# MIRA016-CSP-Sheet1.net
KiCad netlist of a schematic drawn in Altium Designer
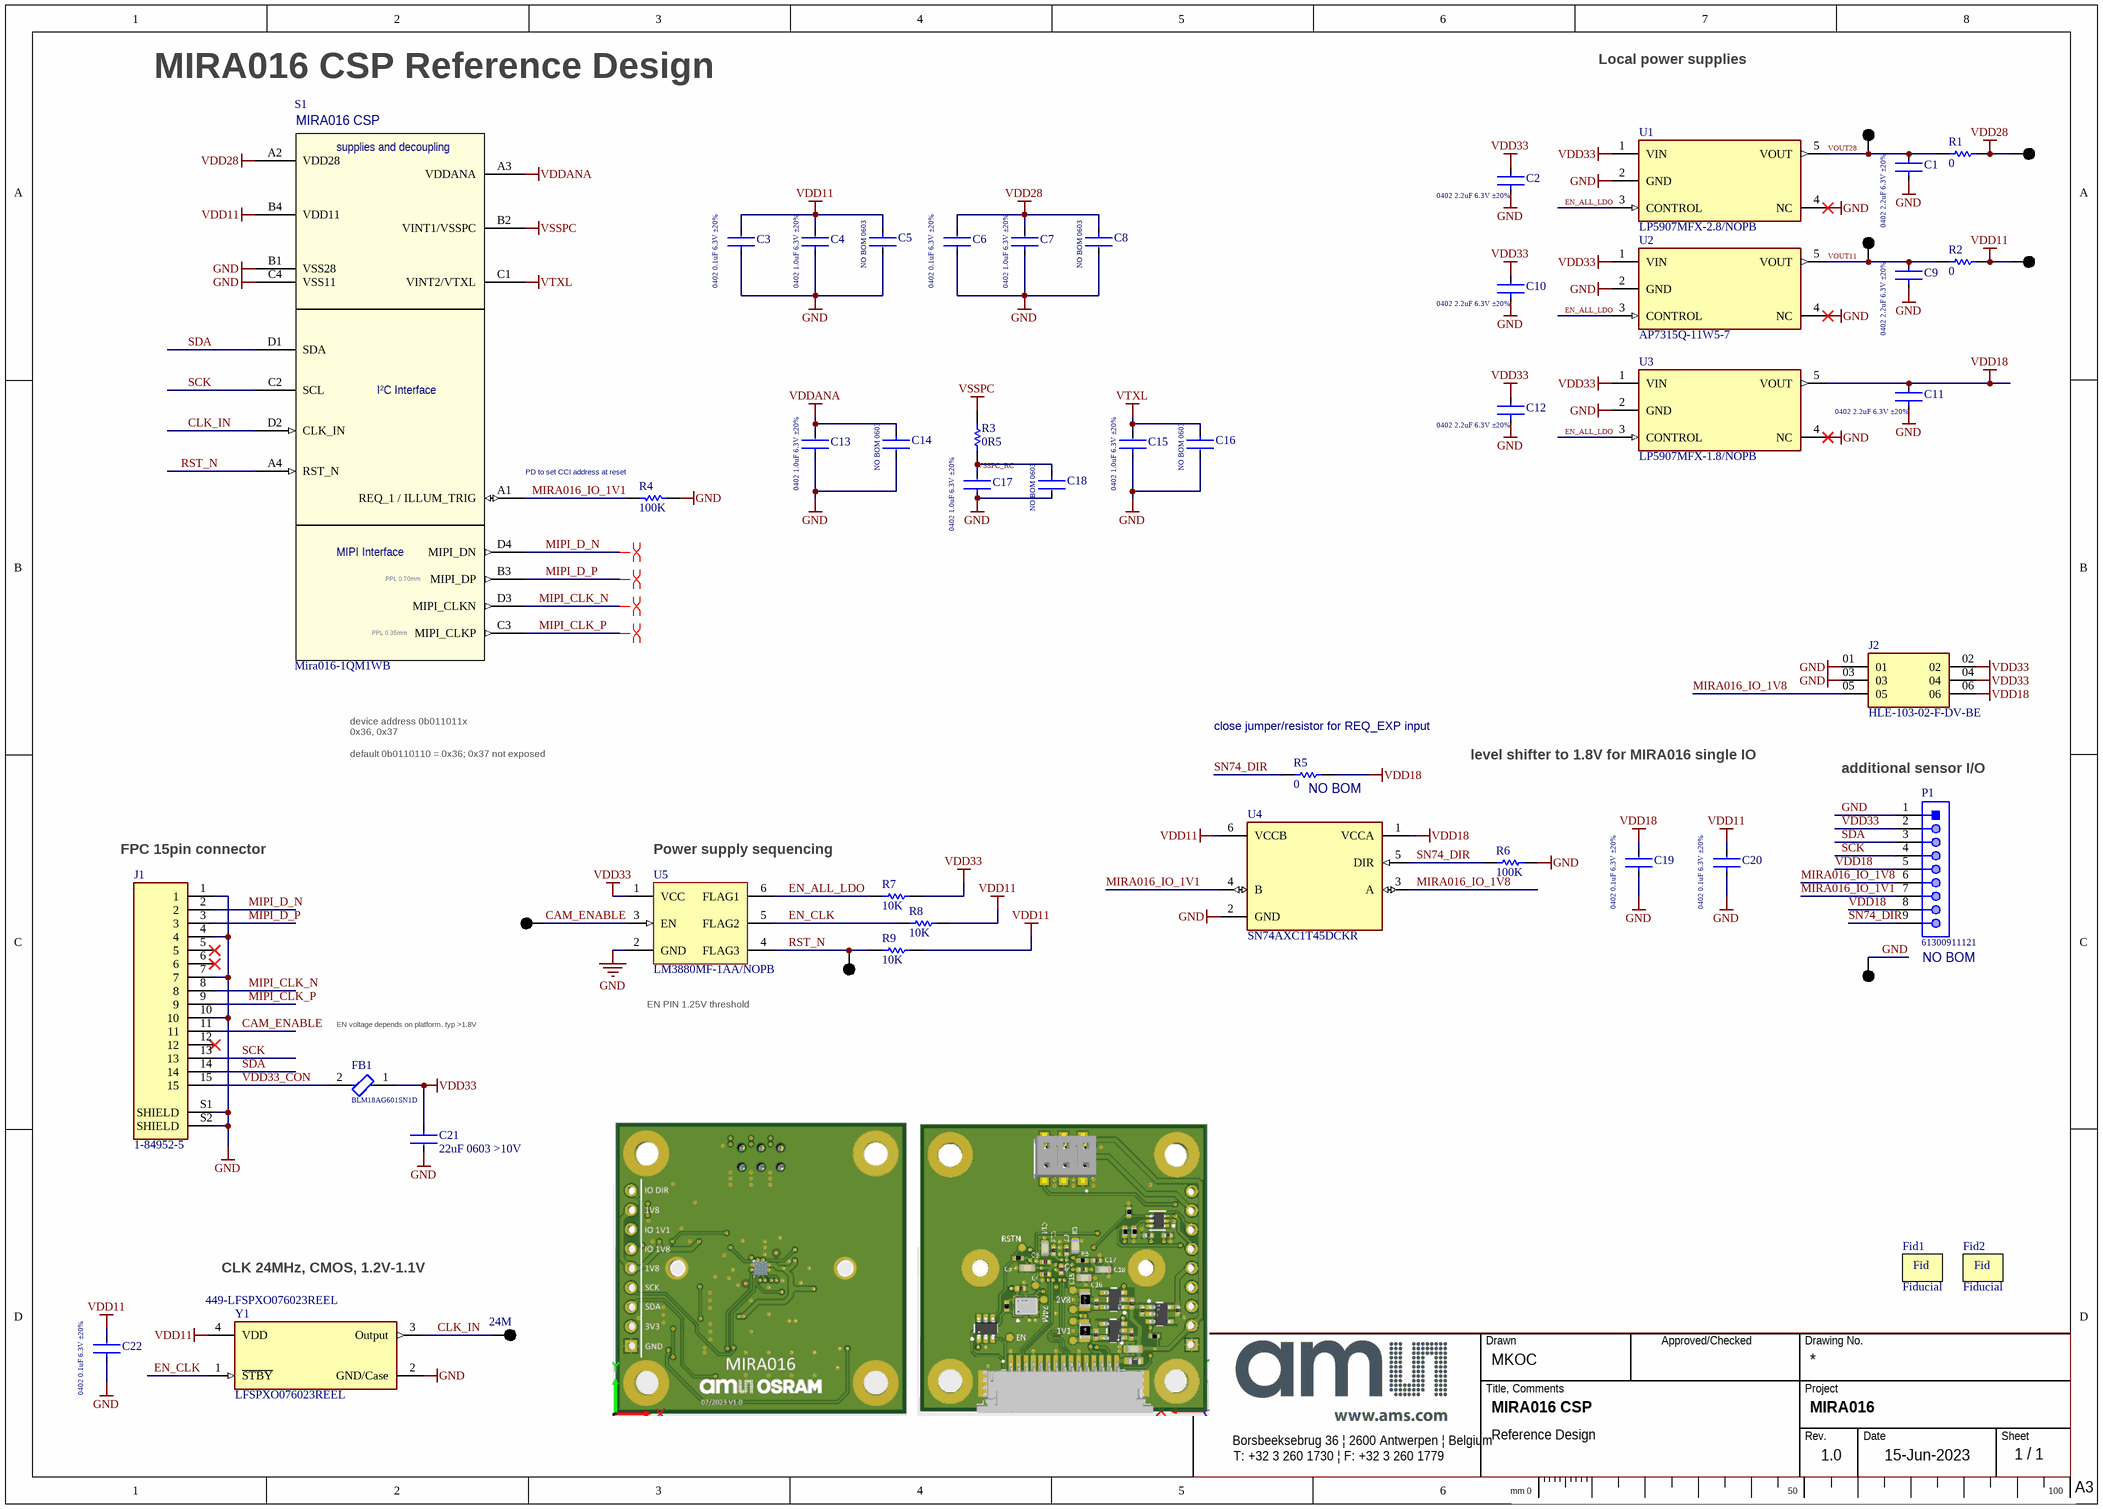
[diagram p0: MIRA016-CSP-Sheet1.SchDoc]

(export (version "E")
  (design (tool "Eeschema 10.0.6"))
  (components
    (comp (ref "C1")
      (value "0402 2.2uF 6.3V ±20%")
      (footprint "CAPC0402_N")
      (description "0402 2.20uF 6.3V ±20%")
      (libsource (lib "MIRA016-COB") (part "CAP0201"))
    )
    (comp (ref "C2")
      (value "0402 2.2uF 6.3V ±20%")
      (footprint "CAPC0402_N")
      (description "0402 2.20uF 6.3V ±20%")
      (libsource (lib "MIRA016-COB") (part "CAP0201"))
    )
    (comp (ref "C3")
      (value "0402 0.1uF 6.3V ±20%")
      (footprint "CAPC0402_N")
      (libsource (lib "MIRA016-COB") (part "CAP0201"))
    )
    (comp (ref "C4")
      (value "0402 1.0uF 6.3V ±20%")
      (footprint "CAPC0402_N")
      (libsource (lib "MIRA016-COB") (part "CAP0201"))
    )
    (comp (ref "C5")
      (value "NO BOM 0603")
      (footprint "CAPC0603_L")
      (description "spare cap 0603")
      (libsource (lib "MIRA016-CSP") (part "CAP0201"))
    )
    (comp (ref "C6")
      (value "0402 0.1uF 6.3V ±20%")
      (footprint "CAPC0402_N")
      (libsource (lib "MIRA016-COB") (part "CAP0201"))
    )
    (comp (ref "C7")
      (value "0402 1.0uF 6.3V ±20%")
      (footprint "CAPC0402_N")
      (libsource (lib "MIRA016-COB") (part "CAP0201"))
    )
    (comp (ref "C8")
      (value "NO BOM 0603")
      (footprint "CAPC0603_L")
      (description "spare cap 0603")
      (libsource (lib "MIRA016-CSP") (part "CAP0201"))
    )
    (comp (ref "C9")
      (value "0402 2.2uF 6.3V ±20%")
      (footprint "CAPC0402_N")
      (description "0402 2.20uF 6.3V ±20%")
      (libsource (lib "MIRA016-COB") (part "CAP0201"))
    )
    (comp (ref "C10")
      (value "0402 2.2uF 6.3V ±20%")
      (footprint "CAPC0402_N")
      (description "0402 2.20uF 6.3V ±20%")
      (libsource (lib "MIRA016-COB") (part "CAP0201"))
    )
    (comp (ref "C11")
      (value "0402 2.2uF 6.3V ±20%")
      (footprint "CAPC0402_N")
      (description "0402 2.20uF 6.3V ±20%")
      (libsource (lib "MIRA016-COB") (part "CAP0201"))
    )
    (comp (ref "C12")
      (value "0402 2.2uF 6.3V ±20%")
      (footprint "CAPC0402_N")
      (description "0402 2.20uF 6.3V ±20%")
      (libsource (lib "MIRA016-COB") (part "CAP0201"))
    )
    (comp (ref "C13")
      (value "0402 1.0uF 6.3V ±20%")
      (footprint "CAPC0402_N")
      (libsource (lib "MIRA016-COB") (part "CAP0201"))
    )
    (comp (ref "C14")
      (value "NO BOM 0603")
      (footprint "CAPC0603_L")
      (description "spare cap 0603")
      (libsource (lib "MIRA016-CSP") (part "CAP0201"))
    )
    (comp (ref "C15")
      (value "0402 1.0uF 6.3V ±20%")
      (footprint "CAPC0402_N")
      (libsource (lib "MIRA016-COB") (part "CAP0201"))
    )
    (comp (ref "C16")
      (value "NO BOM 0603")
      (footprint "CAPC0603_L")
      (description "spare cap 0603")
      (libsource (lib "MIRA016-CSP") (part "CAP0201"))
    )
    (comp (ref "C17")
      (value "0402 1.0uF 6.3V ±20%")
      (footprint "CAPC0402_N")
      (libsource (lib "MIRA016-COB") (part "CAP0201"))
    )
    (comp (ref "C18")
      (value "NO BOM 0603")
      (footprint "CAPC0603_L")
      (description "spare cap 0603")
      (libsource (lib "MIRA016-CSP") (part "CAP0201"))
    )
    (comp (ref "C19")
      (value "0402 0.1uF 6.3V ±20%")
      (footprint "CAPC0402_N")
      (libsource (lib "MIRA016-COB") (part "CAP0201"))
    )
    (comp (ref "C20")
      (value "0402 0.1uF 6.3V ±20%")
      (footprint "CAPC0402_N")
      (libsource (lib "MIRA016-COB") (part "CAP0201"))
    )
    (comp (ref "C21")
      (value "22uF 0603 >10V")
      (footprint "CAPC0603")
      (description "Chip Multilayer Ceramic Capacitors for General Purpose, 0603, 22uF, X5R, 15%, 10%, 25V")
      (libsource (lib "MIRA016-CSP") (part "CAP0201"))
    )
    (comp (ref "C22")
      (value "0402 0.1uF 6.3V ±20%")
      (footprint "CAPC0402_N")
      (libsource (lib "MIRA016-COB") (part "CAP0201"))
    )
    (comp (ref "FB1")
      (value "BLM18AG601SN1D")
      (footprint "FP-BLM18-0_15-t0_8-IPC_B")
      (description "Chip Ferrite Bead, 0603, 600Ω @ 100MHz, 0.38Ω, 25%, 500mA")
      (fields (field (name "TOLERANCE") "25%"))
      (libsource (lib "MIRA050CSP") (part "CMP-0686-00436-3"))
    )
    (comp (ref "Fid1")
      (value "Fiducial")
      (footprint "Fiducial")
      (description "Alignment feature for PCB Assembly")
      (fields (field (name "PART NUMBER") "NA"))
      (libsource (lib "altiumlib") (part "Fiducial"))
    )
    (comp (ref "Fid2")
      (value "Fiducial")
      (footprint "Fiducial")
      (description "Alignment feature for PCB Assembly")
      (fields (field (name "PART NUMBER") "NA"))
      (libsource (lib "altiumlib") (part "Fiducial"))
    )
    (comp (ref "J1")
      (value "1-84952-5")
      (footprint "TE_1-84952-5")
      (description "Conn FPC Connector SKT 15 POS 1mm Solder RA SMD T/R")
      (libsource (lib "MIRA220CSP") (part "1-84952-5"))
    )
    (comp (ref "J2")
      (value "HLE-103-02-F-DV-BE")
      (footprint "SAMTEC_HLE-103-02-F-DV-BE")
      (fields (field (name "MF") "Samtec"))
      (libsource (lib "MIRA016-CSP") (part "HLE-103-02-F-DV-BE"))
    )
    (comp (ref "P1")
      (value "61300911121")
      (footprint "61300911121")
      (description "THT Vertical Pin Header WR-PHD, Pitch 2.54 mm, Single Row, 9 pins")
      (fields (field (name "MANUFACTURER") "Wurth Elektronik") (field (name "PUBLISHER") "WurthElektronik"))
      (libsource (lib "MIRA050CSP") (part "CMP-1502-01080-1"))
    )
    (comp (ref "R1")
      (value "0")
      (footprint "RESC0805_N")
      (description "Resistor 0R 0805")
      (libsource (lib "altiumlib") (part "Res"))
    )
    (comp (ref "R2")
      (value "0")
      (footprint "RESC0805_N")
      (description "Resistor 0R 0805")
      (libsource (lib "altiumlib") (part "Res"))
    )
    (comp (ref "R3")
      (value "0R5")
      (footprint "RESC0402_N")
      (description "Resistor 0R5  0402")
      (libsource (lib "altiumlib") (part "Res"))
    )
    (comp (ref "R4")
      (value "100K")
      (footprint "RESC0402_N")
      (description "Resistor 100K 0402")
      (fields (field (name "PART NUMBER") "ERJ2RKF1502X") (field (name "TOLERANCE") "±1%"))
      (libsource (lib "altiumlib") (part "Res"))
    )
    (comp (ref "R5")
      (value "0")
      (footprint "RESC0402_N")
      (description "Resistor 0 0402")
      (fields (field (name "PART NUMBER") "ERJ2RKF1502X") (field (name "TOLERANCE") "±1%"))
      (libsource (lib "altiumlib") (part "Res"))
    )
    (comp (ref "R6")
      (value "100K")
      (footprint "RESC0402_N")
      (description "Resistor 100K 0402")
      (fields (field (name "PART NUMBER") "ERJ2RKF1502X") (field (name "TOLERANCE") "±1%"))
      (libsource (lib "altiumlib") (part "Res"))
    )
    (comp (ref "R7")
      (value "10K")
      (footprint "RESC0402_N")
      (description "Resistor 10K 0402")
      (fields (field (name "PART NUMBER") "ERJ2RKF1502X") (field (name "TOLERANCE") "±1%"))
      (libsource (lib "altiumlib") (part "Res"))
    )
    (comp (ref "R8")
      (value "10K")
      (footprint "RESC0402_N")
      (description "Resistor 10K 0402")
      (fields (field (name "PART NUMBER") "ERJ2RKF1502X") (field (name "TOLERANCE") "±1%"))
      (libsource (lib "altiumlib") (part "Res"))
    )
    (comp (ref "R9")
      (value "10K")
      (footprint "RESC0402_N")
      (description "Resistor 10K 0402")
      (fields (field (name "PART NUMBER") "ERJ2RKF1502X") (field (name "TOLERANCE") "±1%"))
      (libsource (lib "altiumlib") (part "Res"))
    )
    (comp (ref "S1")
      (value "Mira016-1QM1WB")
      (footprint "MIRA016CSP")
      (description "MIRA016 CSP")
      (libsource (lib "MIRA016-CSP") (part "MIRA016CSP"))
    )
    (comp (ref "TP1")
      (value "2V8")
      (footprint "TP_1mm")
      (description "Test Point, various footprints")
      (libsource (lib "MIRA050CSP") (part "5001"))
    )
    (comp (ref "TP2")
      (value "2V8")
      (footprint "TP_1mm")
      (description "Test Point, various footprints")
      (libsource (lib "MIRA050CSP") (part "5001"))
    )
    (comp (ref "TP3")
      (value "1V1")
      (footprint "TP_1mm")
      (description "Test Point, various footprints")
      (libsource (lib "MIRA050CSP") (part "5001"))
    )
    (comp (ref "TP4")
      (value "1V1")
      (footprint "TP_1mm")
      (description "Test Point, various footprints")
      (libsource (lib "MIRA050CSP") (part "5001"))
    )
    (comp (ref "TP6")
      (value "EN")
      (footprint "TP_1mm")
      (description "Test Point, various footprints")
      (libsource (lib "MIRA050CSP") (part "5001"))
    )
    (comp (ref "TP7")
      (value "RSTN")
      (footprint "TP_1mm")
      (description "Test Point, various footprints")
      (libsource (lib "MIRA050CSP") (part "5001"))
    )
    (comp (ref "TP8")
      (value "GND")
      (footprint "TP_1mm")
      (description "Test Point, various footprints")
      (libsource (lib "MIRA050CSP") (part "5001"))
    )
    (comp (ref "TP9")
      (value "24M")
      (footprint "TP_1mm")
      (description "Test Point, various footprints")
      (libsource (lib "MIRA050CSP") (part "5001"))
    )
    (comp (ref "U1")
      (value "LP5907MFX-2.8/NOPB")
      (footprint "FP-DBV0005A-MFG")
      (description "IC REG LINEAR fixed Voltage, SOT23-5 / SOT-25 / SC74A package")
      (libsource (lib "MIRA016-CSP") (part "LDO-STO23-5"))
    )
    (comp (ref "U2")
      (value "AP7315Q-11W5-7")
      (footprint "FP-DBV0005A-MFG")
      (description "IC REG LINEAR fixed Voltage, SOT23-5 / SOT-25 / SC74A package")
      (libsource (lib "MIRA016-CSP") (part "LDO-STO23-5"))
    )
    (comp (ref "U3")
      (value "LP5907MFX-1.8/NOPB")
      (footprint "FP-DBV0005A-MFG")
      (description "IC REG LINEAR fixed Voltage, SOT23-5 / SOT-25 / SC74A package")
      (libsource (lib "MIRA016-CSP") (part "LDO-STO23-5"))
    )
    (comp (ref "U4")
      (value "SN74AXC1T45DCKR")
      (footprint "FP-DCK0006A-IPC_B")
      (description "IC TRNSLTR BIDIRECTIONAL SC70-6")
      (libsource (lib "Altium Content Vault") (part "d0dbdffe323aa12037fe7fb072119e8"))
    )
    (comp (ref "U5")
      (value "LM3880MF-1AA/NOPB")
      (footprint "DBV0006A_N")
      (description "Power Sequencer, 6-pin SOT-23, Pb-Free, 1000 Reel")
      (libsource (lib "MIRA016-COB") (part "CMP-0063-01015-4"))
    )
    (comp (ref "Y1")
      (value "LFSPXO076023REEL")
      (footprint "FP-ASE-MFG")
      (fields
        (field (name "SUPPLIER PART NUMBER 1") "449-LFSPXO076023REEL")
        (field (name "MANUFACTURER") "IQD")
      )
      (libsource (lib "Altium Content Vault") (part "61a724e6190563596ac712fef61ad37"))
    )
  )
  (nets
    (net (code "1") (name "/CAM_ENABLE") (class "Default")
      (node (ref "J1") (pin "11") (pinfunction "11_11") (pintype "passive"))
      (node (ref "TP6") (pin "1") (pintype "passive"))
      (node (ref "U5") (pin "3") (pinfunction "EN_3") (pintype "input"))
    )
    (net (code "2") (name "/CLK_IN") (class "Default")
      (node (ref "S1") (pin "D2") (pinfunction "CLK_IN_D2") (pintype "input"))
      (node (ref "TP9") (pin "1") (pintype "passive"))
      (node (ref "Y1") (pin "3") (pinfunction "Output_3") (pintype "output"))
    )
    (net (code "3") (name "/EN_ALL_LDO") (class "Default")
      (node (ref "R7") (pin "1") (pinfunction "1_1") (pintype "passive"))
      (node (ref "U1") (pin "3") (pinfunction "CONTROL_3") (pintype "input"))
      (node (ref "U2") (pin "3") (pinfunction "CONTROL_3") (pintype "input"))
      (node (ref "U3") (pin "3") (pinfunction "CONTROL_3") (pintype "input"))
      (node (ref "U5") (pin "6") (pinfunction "FLAG1_6") (pintype "open_collector"))
    )
    (net (code "4") (name "/EN_CLK") (class "Default")
      (node (ref "R8") (pin "1") (pinfunction "1_1") (pintype "passive"))
      (node (ref "U5") (pin "5") (pinfunction "FLAG2_5") (pintype "open_collector"))
      (node (ref "Y1") (pin "1") (pinfunction "~{STBY}_1") (pintype "input"))
    )
    (net (code "5") (name "/MIPI_CLK_N") (class "Default")
      (node (ref "J1") (pin "8") (pinfunction "8_8") (pintype "passive"))
      (node (ref "S1") (pin "D3") (pinfunction "MIPI_CLKN_D3") (pintype "output"))
    )
    (net (code "6") (name "/MIPI_CLK_P") (class "Default")
      (node (ref "J1") (pin "9") (pinfunction "9_9") (pintype "passive"))
      (node (ref "S1") (pin "C3") (pinfunction "MIPI_CLKP_C3") (pintype "output"))
    )
    (net (code "7") (name "/MIPI_D_N") (class "Default")
      (node (ref "J1") (pin "2") (pinfunction "2_2") (pintype "passive"))
      (node (ref "S1") (pin "D4") (pinfunction "MIPI_DN_D4") (pintype "output"))
    )
    (net (code "8") (name "/MIPI_D_P") (class "Default")
      (node (ref "J1") (pin "3") (pinfunction "3_3") (pintype "passive"))
      (node (ref "S1") (pin "B3") (pinfunction "MIPI_DP_B3") (pintype "output"))
    )
    (net (code "9") (name "/MIRA016_IO_1V1") (class "Default")
      (node (ref "P1") (pin "7") (pinfunction "7_7") (pintype "passive"))
      (node (ref "R4") (pin "2") (pinfunction "2_2") (pintype "passive"))
      (node (ref "S1") (pin "A1") (pinfunction "REQ_1_/_ILLUM_TRIG_A1") (pintype "bidirectional"))
      (node (ref "U4") (pin "4") (pinfunction "B_4") (pintype "bidirectional"))
    )
    (net (code "10") (name "/MIRA016_IO_1V8") (class "Default")
      (node (ref "J2") (pin "05") (pinfunction "05_05") (pintype "passive"))
      (node (ref "P1") (pin "6") (pinfunction "6_6") (pintype "passive"))
      (node (ref "U4") (pin "3") (pinfunction "A_3") (pintype "bidirectional"))
    )
    (net (code "11") (name "/RST_N") (class "Default")
      (node (ref "R9") (pin "1") (pinfunction "1_1") (pintype "passive"))
      (node (ref "S1") (pin "A4") (pinfunction "RST_N_A4") (pintype "input"))
      (node (ref "TP7") (pin "1") (pintype "passive"))
      (node (ref "U5") (pin "4") (pinfunction "FLAG3_4") (pintype "open_collector"))
    )
    (net (code "12") (name "/SCK") (class "Default")
      (node (ref "J1") (pin "13") (pinfunction "13_13") (pintype "passive"))
      (node (ref "P1") (pin "4") (pinfunction "4_4") (pintype "passive"))
      (node (ref "S1") (pin "C2") (pinfunction "SCL_C2") (pintype "open_collector"))
    )
    (net (code "13") (name "/SDA") (class "Default")
      (node (ref "J1") (pin "14") (pinfunction "14_14") (pintype "passive"))
      (node (ref "P1") (pin "3") (pinfunction "3_3") (pintype "passive"))
      (node (ref "S1") (pin "D1") (pinfunction "SDA_D1") (pintype "open_collector"))
    )
    (net (code "14") (name "/SN74_DIR") (class "Default")
      (node (ref "P1") (pin "9") (pinfunction "9_9") (pintype "passive"))
      (node (ref "R5") (pin "1") (pinfunction "1_1") (pintype "passive"))
      (node (ref "R6") (pin "2") (pinfunction "2_2") (pintype "passive"))
      (node (ref "U4") (pin "5") (pinfunction "DIR_5") (pintype "input"))
    )
    (net (code "15") (name "/VDD33_CON") (class "Default")
      (node (ref "FB1") (pin "2") (pinfunction "2_2") (pintype "passive"))
      (node (ref "J1") (pin "15") (pinfunction "15_15") (pintype "passive"))
    )
    (net (code "16") (name "/VOUT11") (class "Default")
      (node (ref "C9") (pin "2") (pinfunction "2_2") (pintype "passive"))
      (node (ref "R2") (pin "2") (pinfunction "2_2") (pintype "passive"))
      (node (ref "TP3") (pin "1") (pintype "passive"))
      (node (ref "U2") (pin "5") (pinfunction "VOUT_5") (pintype "output"))
    )
    (net (code "17") (name "/VOUT28") (class "Default")
      (node (ref "C1") (pin "2") (pinfunction "2_2") (pintype "passive"))
      (node (ref "R1") (pin "2") (pinfunction "2_2") (pintype "passive"))
      (node (ref "TP1") (pin "1") (pintype "passive"))
      (node (ref "U1") (pin "5") (pinfunction "VOUT_5") (pintype "output"))
    )
    (net (code "18") (name "/VSSPC_RC") (class "Default")
      (node (ref "C17") (pin "2") (pinfunction "2_2") (pintype "passive"))
      (node (ref "C18") (pin "1") (pinfunction "1_1") (pintype "passive"))
      (node (ref "R3") (pin "1") (pinfunction "1_1") (pintype "passive"))
    )
    (net (code "19") (name "GND") (class "Default")
      (node (ref "C1") (pin "1") (pinfunction "1_1") (pintype "passive"))
      (node (ref "C10") (pin "1") (pinfunction "1_1") (pintype "passive"))
      (node (ref "C11") (pin "1") (pinfunction "1_1") (pintype "passive"))
      (node (ref "C12") (pin "1") (pinfunction "1_1") (pintype "passive"))
      (node (ref "C13") (pin "1") (pinfunction "1_1") (pintype "passive"))
      (node (ref "C14") (pin "2") (pinfunction "2_2") (pintype "passive"))
      (node (ref "C15") (pin "1") (pinfunction "1_1") (pintype "passive"))
      (node (ref "C16") (pin "2") (pinfunction "2_2") (pintype "passive"))
      (node (ref "C17") (pin "1") (pinfunction "1_1") (pintype "passive"))
      (node (ref "C18") (pin "2") (pinfunction "2_2") (pintype "passive"))
      (node (ref "C19") (pin "1") (pinfunction "1_1") (pintype "passive"))
      (node (ref "C2") (pin "1") (pinfunction "1_1") (pintype "passive"))
      (node (ref "C20") (pin "1") (pinfunction "1_1") (pintype "passive"))
      (node (ref "C21") (pin "2") (pinfunction "2_2") (pintype "passive"))
      (node (ref "C22") (pin "1") (pinfunction "1_1") (pintype "passive"))
      (node (ref "C3") (pin "1") (pinfunction "1_1") (pintype "passive"))
      (node (ref "C4") (pin "1") (pinfunction "1_1") (pintype "passive"))
      (node (ref "C5") (pin "2") (pinfunction "2_2") (pintype "passive"))
      (node (ref "C6") (pin "1") (pinfunction "1_1") (pintype "passive"))
      (node (ref "C7") (pin "1") (pinfunction "1_1") (pintype "passive"))
      (node (ref "C8") (pin "2") (pinfunction "2_2") (pintype "passive"))
      (node (ref "C9") (pin "1") (pinfunction "1_1") (pintype "passive"))
      (node (ref "J1") (pin "1") (pinfunction "1_1") (pintype "passive"))
      (node (ref "J1") (pin "10") (pinfunction "10_10") (pintype "passive"))
      (node (ref "J1") (pin "4") (pinfunction "4_4") (pintype "passive"))
      (node (ref "J1") (pin "7") (pinfunction "7_7") (pintype "passive"))
      (node (ref "J1") (pin "S1") (pinfunction "SHIELD_S1") (pintype "passive"))
      (node (ref "J1") (pin "S2") (pinfunction "SHIELD_S2") (pintype "passive"))
      (node (ref "J2") (pin "01") (pinfunction "01_01") (pintype "passive"))
      (node (ref "J2") (pin "03") (pinfunction "03_03") (pintype "passive"))
      (node (ref "P1") (pin "1") (pinfunction "1_1") (pintype "passive"))
      (node (ref "R4") (pin "1") (pinfunction "1_1") (pintype "passive"))
      (node (ref "R6") (pin "1") (pinfunction "1_1") (pintype "passive"))
      (node (ref "S1") (pin "B1") (pinfunction "VSS28_B1") (pintype "power_in"))
      (node (ref "S1") (pin "C4") (pinfunction "VSS11_C4") (pintype "power_in"))
      (node (ref "TP8") (pin "1") (pintype "passive"))
      (node (ref "U1") (pin "2") (pinfunction "GND_2") (pintype "power_in"))
      (node (ref "U1") (pin "4") (pinfunction "NC_4") (pintype "passive"))
      (node (ref "U2") (pin "2") (pinfunction "GND_2") (pintype "power_in"))
      (node (ref "U2") (pin "4") (pinfunction "NC_4") (pintype "passive"))
      (node (ref "U3") (pin "2") (pinfunction "GND_2") (pintype "power_in"))
      (node (ref "U3") (pin "4") (pinfunction "NC_4") (pintype "passive"))
      (node (ref "U4") (pin "2") (pinfunction "GND_2") (pintype "power_in"))
      (node (ref "U5") (pin "2") (pinfunction "GND_2") (pintype "power_in"))
      (node (ref "Y1") (pin "2") (pinfunction "GND/Case_2") (pintype "power_in"))
    )
    (net (code "20") (name "VDD11") (class "Default")
      (node (ref "C20") (pin "2") (pinfunction "2_2") (pintype "passive"))
      (node (ref "C22") (pin "2") (pinfunction "2_2") (pintype "passive"))
      (node (ref "C3") (pin "2") (pinfunction "2_2") (pintype "passive"))
      (node (ref "C4") (pin "2") (pinfunction "2_2") (pintype "passive"))
      (node (ref "C5") (pin "1") (pinfunction "1_1") (pintype "passive"))
      (node (ref "R2") (pin "1") (pinfunction "1_1") (pintype "passive"))
      (node (ref "R8") (pin "2") (pinfunction "2_2") (pintype "passive"))
      (node (ref "R9") (pin "2") (pinfunction "2_2") (pintype "passive"))
      (node (ref "S1") (pin "B4") (pinfunction "VDD11_B4") (pintype "power_in"))
      (node (ref "TP4") (pin "1") (pintype "passive"))
      (node (ref "U4") (pin "6") (pinfunction "VCCB_6") (pintype "power_in"))
      (node (ref "Y1") (pin "4") (pinfunction "VDD_4") (pintype "power_in"))
    )
    (net (code "21") (name "VDD18") (class "Default")
      (node (ref "C11") (pin "2") (pinfunction "2_2") (pintype "passive"))
      (node (ref "C19") (pin "2") (pinfunction "2_2") (pintype "passive"))
      (node (ref "J2") (pin "06") (pinfunction "06_06") (pintype "passive"))
      (node (ref "P1") (pin "5") (pinfunction "5_5") (pintype "passive"))
      (node (ref "P1") (pin "8") (pinfunction "8_8") (pintype "passive"))
      (node (ref "R5") (pin "2") (pinfunction "2_2") (pintype "passive"))
      (node (ref "U3") (pin "5") (pinfunction "VOUT_5") (pintype "output"))
      (node (ref "U4") (pin "1") (pinfunction "VCCA_1") (pintype "power_in"))
    )
    (net (code "22") (name "VDD28") (class "Default")
      (node (ref "C6") (pin "2") (pinfunction "2_2") (pintype "passive"))
      (node (ref "C7") (pin "2") (pinfunction "2_2") (pintype "passive"))
      (node (ref "C8") (pin "1") (pinfunction "1_1") (pintype "passive"))
      (node (ref "R1") (pin "1") (pinfunction "1_1") (pintype "passive"))
      (node (ref "S1") (pin "A2") (pinfunction "VDD28_A2") (pintype "power_in"))
      (node (ref "TP2") (pin "1") (pintype "passive"))
    )
    (net (code "23") (name "VDD33") (class "Default")
      (node (ref "C10") (pin "2") (pinfunction "2_2") (pintype "passive"))
      (node (ref "C12") (pin "2") (pinfunction "2_2") (pintype "passive"))
      (node (ref "C2") (pin "2") (pinfunction "2_2") (pintype "passive"))
      (node (ref "C21") (pin "1") (pinfunction "1_1") (pintype "passive"))
      (node (ref "FB1") (pin "1") (pinfunction "1_1") (pintype "passive"))
      (node (ref "J2") (pin "02") (pinfunction "02_02") (pintype "passive"))
      (node (ref "J2") (pin "04") (pinfunction "04_04") (pintype "passive"))
      (node (ref "P1") (pin "2") (pinfunction "2_2") (pintype "passive"))
      (node (ref "R7") (pin "2") (pinfunction "2_2") (pintype "passive"))
      (node (ref "U1") (pin "1") (pinfunction "VIN_1") (pintype "power_in"))
      (node (ref "U2") (pin "1") (pinfunction "VIN_1") (pintype "power_in"))
      (node (ref "U3") (pin "1") (pinfunction "VIN_1") (pintype "power_in"))
      (node (ref "U5") (pin "1") (pinfunction "VCC_1") (pintype "power_in"))
    )
    (net (code "24") (name "VDDANA") (class "Default")
      (node (ref "C13") (pin "2") (pinfunction "2_2") (pintype "passive"))
      (node (ref "C14") (pin "1") (pinfunction "1_1") (pintype "passive"))
      (node (ref "S1") (pin "A3") (pinfunction "VDDANA_A3") (pintype "passive"))
    )
    (net (code "25") (name "VSSPC") (class "Default")
      (node (ref "R3") (pin "2") (pinfunction "2_2") (pintype "passive"))
      (node (ref "S1") (pin "B2") (pinfunction "VINT1/VSSPC_B2") (pintype "passive"))
    )
    (net (code "26") (name "VTXL") (class "Default")
      (node (ref "C15") (pin "2") (pinfunction "2_2") (pintype "passive"))
      (node (ref "C16") (pin "1") (pinfunction "1_1") (pintype "passive"))
      (node (ref "S1") (pin "C1") (pinfunction "VINT2/VTXL_C1") (pintype "passive"))
    )
    (net (code "27") (name "unconnected-(J1-Pad5)") (class "Default")
      (node (ref "J1") (pin "5") (pinfunction "5_5") (pintype "passive+no_connect"))
    )
    (net (code "28") (name "unconnected-(J1-Pad6)") (class "Default")
      (node (ref "J1") (pin "6") (pinfunction "6_6") (pintype "passive+no_connect"))
    )
    (net (code "29") (name "unconnected-(J1-Pad12)") (class "Default")
      (node (ref "J1") (pin "12") (pinfunction "12_12") (pintype "passive+no_connect"))
    )
  )
)
